# pth_supply_servos.net
KiCad netlist of a schematic drawn in EAGLE
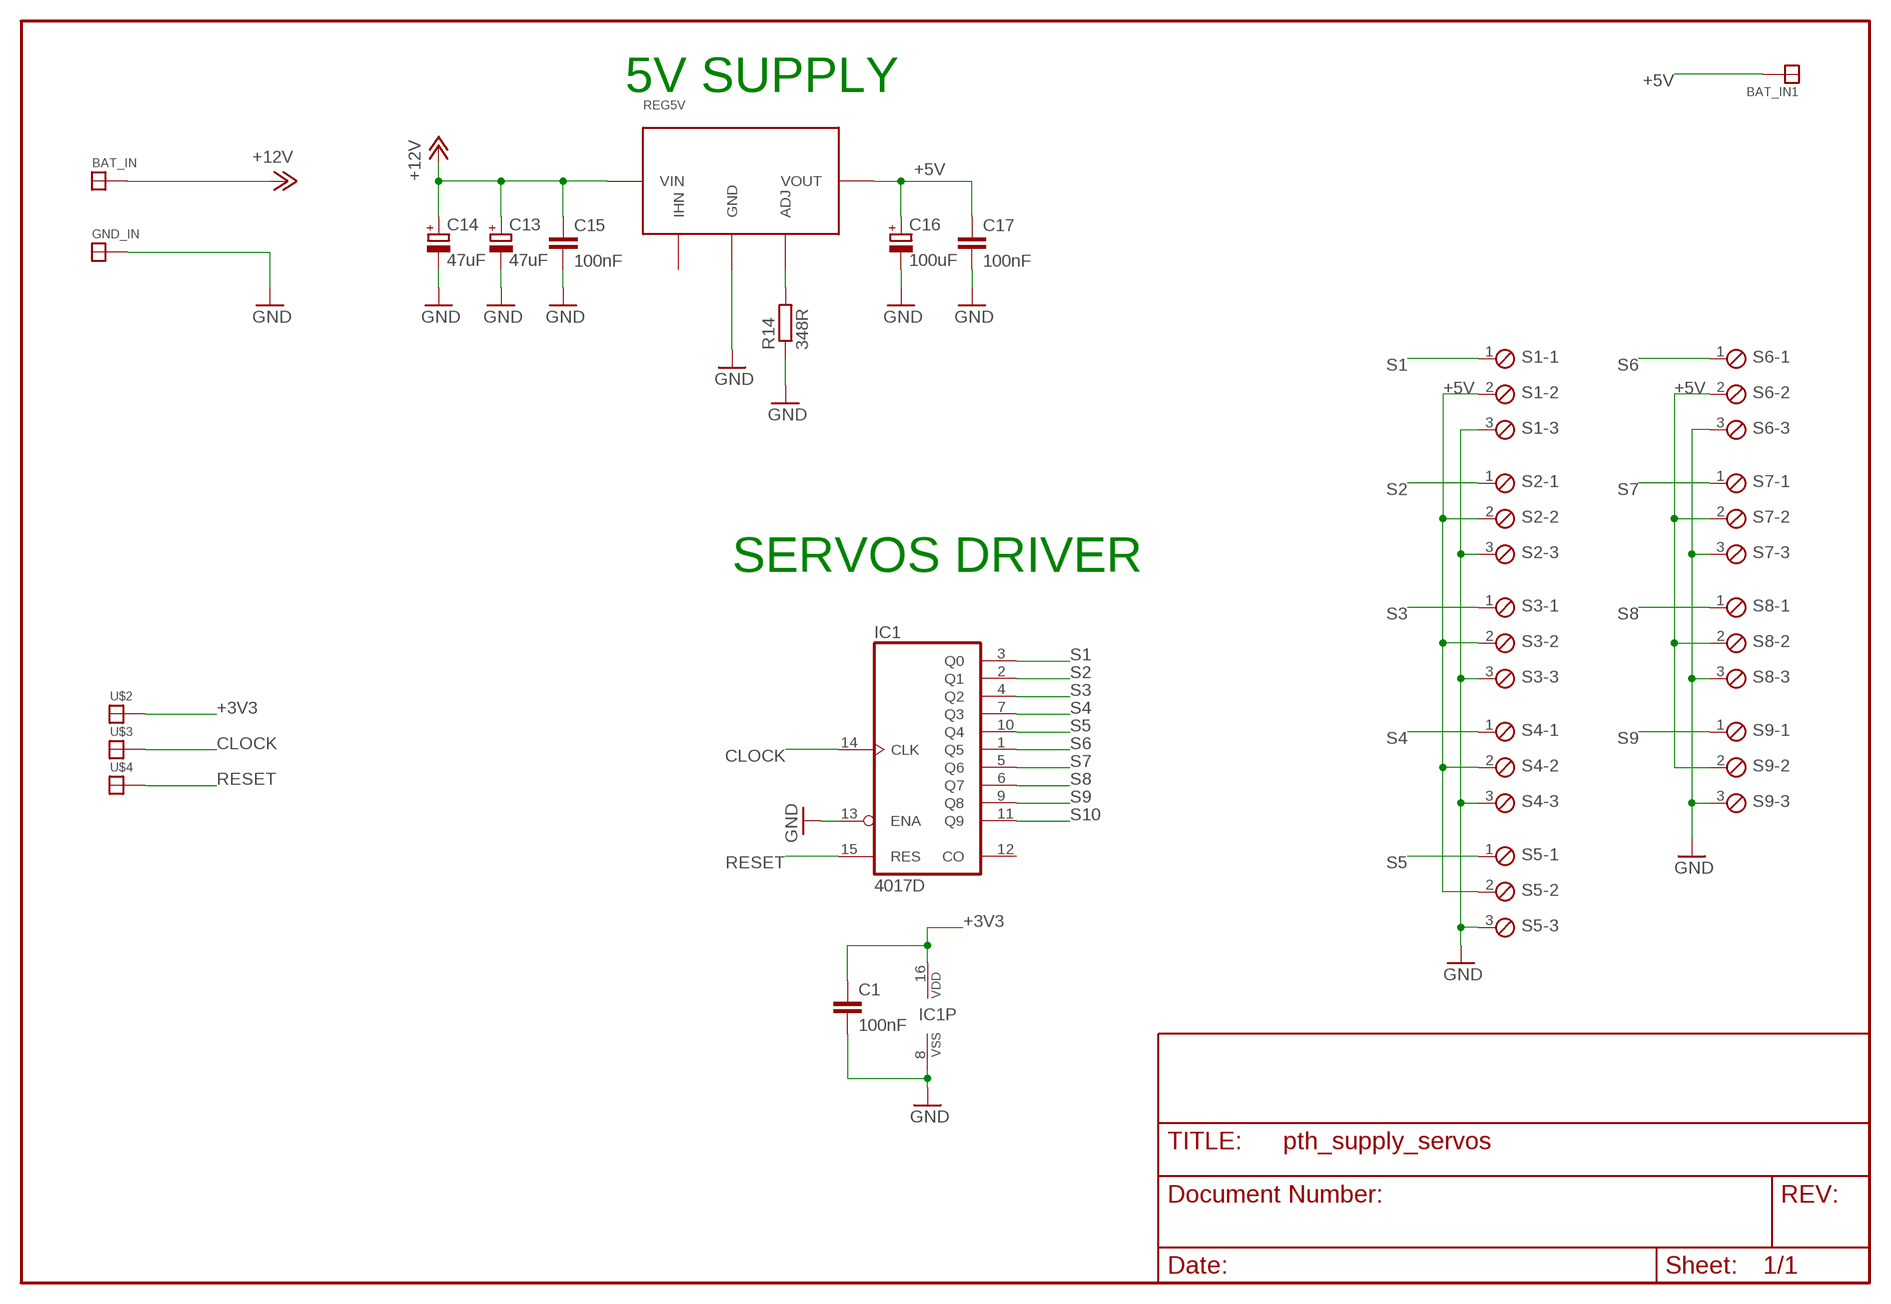
[diagram p0: schematic, sheet 1]

(export (version "E")
  (design (tool "Eeschema 10.0.6"))
  (components
    (comp (ref "BAT_IN")
      (value "SOLDER_PAD150_75")
      (footprint "eagle-import:SOLD_PAD_150_75")
      (libsource (lib "eagle-import") (part "SOLDER_PAD150_75"))
    )
    (comp (ref "BAT_IN1")
      (value "SOLDER_PAD150_75")
      (footprint "eagle-import:SOLD_PAD_150_75")
      (libsource (lib "eagle-import") (part "SOLDER_PAD150_75"))
    )
    (comp (ref "C1")
      (value "100nF")
      (footprint "eagle-import:C0805K")
      (libsource (lib "eagle-import") (part "C-EUC0805K"))
    )
    (comp (ref "C13")
      (value "47uF")
      (footprint "eagle-import:SMC_D")
      (libsource (lib "eagle-import") (part "CPOL-EUSMCD"))
    )
    (comp (ref "C14")
      (value "47uF")
      (footprint "eagle-import:SMC_D")
      (libsource (lib "eagle-import") (part "CPOL-EUSMCD"))
    )
    (comp (ref "C15")
      (value "100nF")
      (footprint "eagle-import:C0805K")
      (libsource (lib "eagle-import") (part "C-EUC0805K"))
    )
    (comp (ref "C16")
      (value "100uF")
      (footprint "eagle-import:SMC_D")
      (libsource (lib "eagle-import") (part "CPOL-EUSMCD"))
    )
    (comp (ref "C17")
      (value "100nF")
      (footprint "eagle-import:C0805K")
      (libsource (lib "eagle-import") (part "C-EUC0805K"))
    )
    (comp (ref "GND_IN")
      (value "SOLDER_PAD150_75")
      (footprint "eagle-import:SOLD_PAD_150_75")
      (libsource (lib "eagle-import") (part "SOLDER_PAD150_75"))
    )
    (comp (ref "IC1")
      (value "4017D")
      (footprint "eagle-import:SO16")
      (libsource (lib "eagle-import") (part "4017D"))
    )
    (comp (ref "R14")
      (value "348R")
      (footprint "eagle-import:R0805")
      (libsource (lib "eagle-import") (part "R-EU_R0805"))
    )
    (comp (ref "REG5V")
      (value "PTH")
      (footprint "eagle-import:PTH")
      (libsource (lib "eagle-import") (part "PTH"))
    )
    (comp (ref "S1")
      (value "MPT3")
      (footprint "eagle-import:3POL254")
      (libsource (lib "eagle-import") (part "MPT3"))
    )
    (comp (ref "S2")
      (value "MPT3")
      (footprint "eagle-import:3POL254")
      (libsource (lib "eagle-import") (part "MPT3"))
    )
    (comp (ref "S3")
      (value "MPT3")
      (footprint "eagle-import:3POL254")
      (libsource (lib "eagle-import") (part "MPT3"))
    )
    (comp (ref "S4")
      (value "MPT3")
      (footprint "eagle-import:3POL254")
      (libsource (lib "eagle-import") (part "MPT3"))
    )
    (comp (ref "S5")
      (value "MPT3")
      (footprint "eagle-import:3POL254")
      (libsource (lib "eagle-import") (part "MPT3"))
    )
    (comp (ref "S6")
      (value "MPT3")
      (footprint "eagle-import:3POL254")
      (libsource (lib "eagle-import") (part "MPT3"))
    )
    (comp (ref "S7")
      (value "MPT3")
      (footprint "eagle-import:3POL254")
      (libsource (lib "eagle-import") (part "MPT3"))
    )
    (comp (ref "S8")
      (value "MPT3")
      (footprint "eagle-import:3POL254")
      (libsource (lib "eagle-import") (part "MPT3"))
    )
    (comp (ref "S9")
      (value "MPT3")
      (footprint "eagle-import:3POL254")
      (libsource (lib "eagle-import") (part "MPT3"))
    )
    (comp (ref "U$2")
      (value "SOLDER_PAD100_50")
      (footprint "eagle-import:SOLDER_PAD_100_50")
      (libsource (lib "eagle-import") (part "SOLDER_PAD100_50"))
    )
    (comp (ref "U$3")
      (value "SOLDER_PAD100_50")
      (footprint "eagle-import:SOLDER_PAD_100_50")
      (libsource (lib "eagle-import") (part "SOLDER_PAD100_50"))
    )
    (comp (ref "U$4")
      (value "SOLDER_PAD100_50")
      (footprint "eagle-import:SOLDER_PAD_100_50")
      (libsource (lib "eagle-import") (part "SOLDER_PAD100_50"))
    )
  )
  (nets
    (net (code "1") (name "+12V") (class "Default")
      (node (ref "BAT_IN") (pin "P$1") (pinfunction "P$1_P$1") (pintype "bidirectional"))
      (node (ref "C13") (pin "+") (pinfunction "+_+") (pintype "passive"))
      (node (ref "C14") (pin "+") (pinfunction "+_+") (pintype "passive"))
      (node (ref "C15") (pin "1") (pinfunction "1_1") (pintype "passive"))
      (node (ref "REG5V") (pin "P$1") (pinfunction "VIN_P$1") (pintype "bidirectional"))
    )
    (net (code "2") (name "/+3V3") (class "Default")
      (node (ref "C1") (pin "1") (pinfunction "1_1") (pintype "passive"))
      (node (ref "IC1") (pin "16") (pinfunction "VDD_16") (pintype "power_in"))
      (node (ref "U$2") (pin "P$1") (pinfunction "P$1_P$1") (pintype "bidirectional"))
    )
    (net (code "3") (name "/+5V") (class "Default")
      (node (ref "BAT_IN1") (pin "P$1") (pinfunction "P$1_P$1") (pintype "bidirectional"))
      (node (ref "C16") (pin "+") (pinfunction "+_+") (pintype "passive"))
      (node (ref "C17") (pin "1") (pinfunction "1_1") (pintype "passive"))
      (node (ref "REG5V") (pin "P$3") (pinfunction "VOUT_P$3") (pintype "bidirectional"))
      (node (ref "S1") (pin "2") (pinfunction "1_2") (pintype "passive"))
      (node (ref "S2") (pin "2") (pinfunction "1_2") (pintype "passive"))
      (node (ref "S3") (pin "2") (pinfunction "1_2") (pintype "passive"))
      (node (ref "S4") (pin "2") (pinfunction "1_2") (pintype "passive"))
      (node (ref "S5") (pin "2") (pinfunction "1_2") (pintype "passive"))
      (node (ref "S6") (pin "2") (pinfunction "1_2") (pintype "passive"))
      (node (ref "S7") (pin "2") (pinfunction "1_2") (pintype "passive"))
      (node (ref "S8") (pin "2") (pinfunction "1_2") (pintype "passive"))
      (node (ref "S9") (pin "2") (pinfunction "1_2") (pintype "passive"))
    )
    (net (code "4") (name "/CLOCK") (class "Default")
      (node (ref "IC1") (pin "14") (pinfunction "CLK_14") (pintype "input"))
      (node (ref "U$3") (pin "P$1") (pinfunction "P$1_P$1") (pintype "bidirectional"))
    )
    (net (code "5") (name "/RESET") (class "Default")
      (node (ref "IC1") (pin "15") (pinfunction "RES_15") (pintype "input"))
      (node (ref "U$4") (pin "P$1") (pinfunction "P$1_P$1") (pintype "bidirectional"))
    )
    (net (code "6") (name "/S1") (class "Default")
      (node (ref "IC1") (pin "3") (pinfunction "Q0_3") (pintype "output"))
      (node (ref "S1") (pin "1") (pinfunction "1_1") (pintype "passive"))
    )
    (net (code "7") (name "/S2") (class "Default")
      (node (ref "IC1") (pin "2") (pinfunction "Q1_2") (pintype "output"))
      (node (ref "S2") (pin "1") (pinfunction "1_1") (pintype "passive"))
    )
    (net (code "8") (name "/S3") (class "Default")
      (node (ref "IC1") (pin "4") (pinfunction "Q2_4") (pintype "output"))
      (node (ref "S3") (pin "1") (pinfunction "1_1") (pintype "passive"))
    )
    (net (code "9") (name "/S4") (class "Default")
      (node (ref "IC1") (pin "7") (pinfunction "Q3_7") (pintype "output"))
      (node (ref "S4") (pin "1") (pinfunction "1_1") (pintype "passive"))
    )
    (net (code "10") (name "/S5") (class "Default")
      (node (ref "IC1") (pin "10") (pinfunction "Q4_10") (pintype "output"))
      (node (ref "S5") (pin "1") (pinfunction "1_1") (pintype "passive"))
    )
    (net (code "11") (name "/S6") (class "Default")
      (node (ref "IC1") (pin "1") (pinfunction "Q5_1") (pintype "output"))
      (node (ref "S6") (pin "1") (pinfunction "1_1") (pintype "passive"))
    )
    (net (code "12") (name "/S7") (class "Default")
      (node (ref "IC1") (pin "5") (pinfunction "Q6_5") (pintype "output"))
      (node (ref "S7") (pin "1") (pinfunction "1_1") (pintype "passive"))
    )
    (net (code "13") (name "/S8") (class "Default")
      (node (ref "IC1") (pin "6") (pinfunction "Q7_6") (pintype "output"))
      (node (ref "S8") (pin "1") (pinfunction "1_1") (pintype "passive"))
    )
    (net (code "14") (name "/S9") (class "Default")
      (node (ref "IC1") (pin "9") (pinfunction "Q8_9") (pintype "output"))
      (node (ref "S9") (pin "1") (pinfunction "1_1") (pintype "passive"))
    )
    (net (code "15") (name "/S10") (class "Default")
      (node (ref "IC1") (pin "11") (pinfunction "Q9_11") (pintype "output"))
    )
    (net (code "16") (name "GND") (class "Default")
      (node (ref "C1") (pin "2") (pinfunction "2_2") (pintype "passive"))
      (node (ref "C13") (pin "-") (pinfunction "-_-") (pintype "passive"))
      (node (ref "C14") (pin "-") (pinfunction "-_-") (pintype "passive"))
      (node (ref "C15") (pin "2") (pinfunction "2_2") (pintype "passive"))
      (node (ref "C16") (pin "-") (pinfunction "-_-") (pintype "passive"))
      (node (ref "C17") (pin "2") (pinfunction "2_2") (pintype "passive"))
      (node (ref "GND_IN") (pin "P$1") (pinfunction "P$1_P$1") (pintype "bidirectional"))
      (node (ref "IC1") (pin "13") (pinfunction "ENA_13") (pintype "input"))
      (node (ref "IC1") (pin "8") (pinfunction "VSS_8") (pintype "power_in"))
      (node (ref "R14") (pin "1") (pinfunction "1_1") (pintype "passive"))
      (node (ref "REG5V") (pin "P$2") (pinfunction "GND_P$2") (pintype "bidirectional"))
      (node (ref "S1") (pin "3") (pinfunction "1_3") (pintype "passive"))
      (node (ref "S2") (pin "3") (pinfunction "1_3") (pintype "passive"))
      (node (ref "S3") (pin "3") (pinfunction "1_3") (pintype "passive"))
      (node (ref "S4") (pin "3") (pinfunction "1_3") (pintype "passive"))
      (node (ref "S5") (pin "3") (pinfunction "1_3") (pintype "passive"))
      (node (ref "S6") (pin "3") (pinfunction "1_3") (pintype "passive"))
      (node (ref "S7") (pin "3") (pinfunction "1_3") (pintype "passive"))
      (node (ref "S8") (pin "3") (pinfunction "1_3") (pintype "passive"))
      (node (ref "S9") (pin "3") (pinfunction "1_3") (pintype "passive"))
    )
    (net (code "17") (name "Net-(REG5V-ADJ)") (class "Default")
      (node (ref "R14") (pin "2") (pinfunction "2_2") (pintype "passive"))
      (node (ref "REG5V") (pin "P$4") (pinfunction "ADJ_P$4") (pintype "bidirectional"))
    )
    (net (code "18") (name "unconnected-(IC1A-CO-Pad12)") (class "Default")
      (node (ref "IC1") (pin "12") (pinfunction "CO_12") (pintype "output"))
    )
    (net (code "19") (name "unconnected-(REG5V-IHN-PadP$5)") (class "Default")
      (node (ref "REG5V") (pin "P$5") (pinfunction "IHN_P$5") (pintype "bidirectional"))
    )
  )
)
